# M8-SHT30.net
KiCad netlist of a schematic drawn in EAGLE
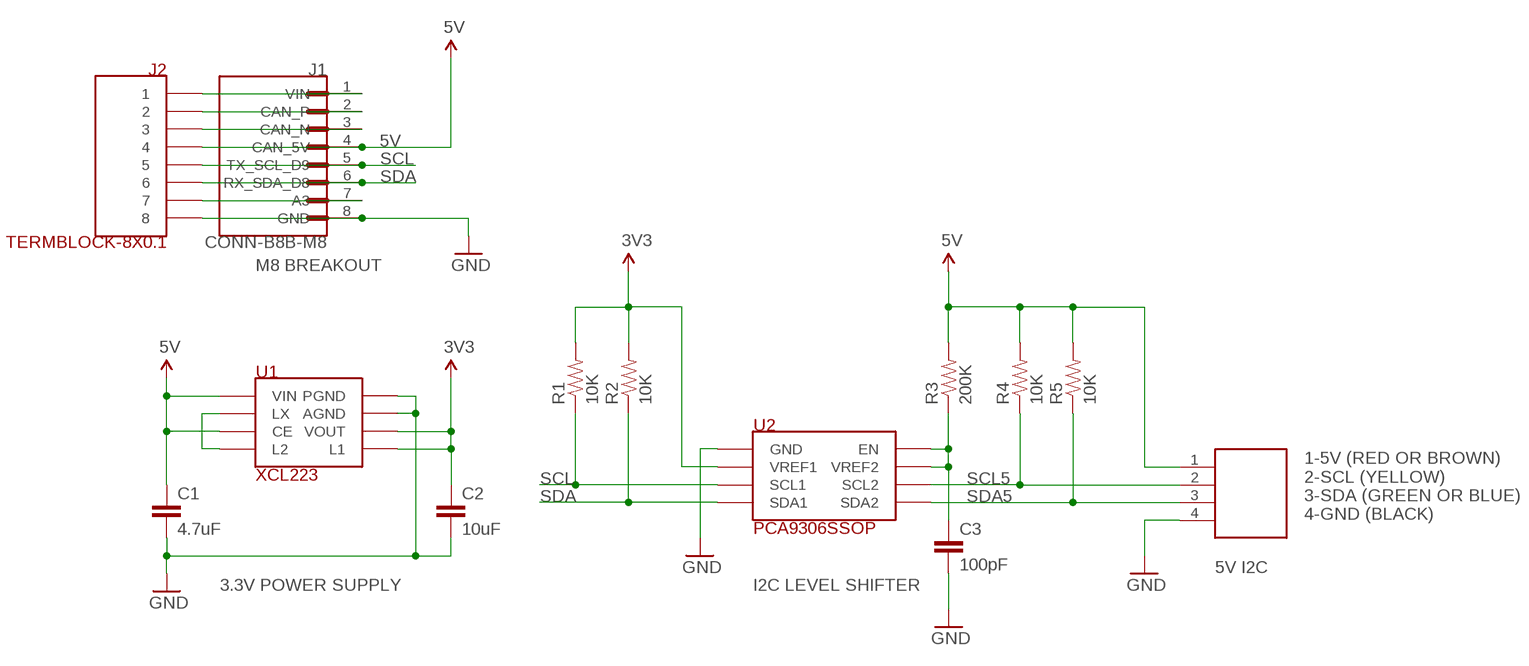
[diagram p0: schematic, sheet 1]

(export (version "E")
  (design (tool "Eeschema 10.0.6"))
  (components
    (comp (ref "C1")
      (value "4.7uF")
      (footprint "eagle-import:0603-CAP")
      (libsource (lib "eagle-import") (part "CAP-4.7UF-0603"))
    )
    (comp (ref "C2")
      (value "10uF")
      (footprint "eagle-import:0603-CAP")
      (libsource (lib "eagle-import") (part "CAP-10UF-0603"))
    )
    (comp (ref "C3")
      (value "100pF")
      (footprint "eagle-import:0603-CAP")
      (libsource (lib "eagle-import") (part "CAP-100PF-0603"))
    )
    (comp (ref "J1")
      (value "CONN-B8B-M8")
      (footprint "eagle-import:JST_B8B-PH-SM4-TB(LF)(SN)")
      (libsource (lib "eagle-import") (part "CONN-B8B-M8"))
    )
    (comp (ref "J2")
      (value "TERMBLOCK-8X0.1")
      (footprint "eagle-import:TERMBLOCK-8X0.1")
      (libsource (lib "eagle-import") (part "TERMBLOCK-8X0.1"))
    )
    (comp (ref "R1")
      (value "10K")
      (footprint "eagle-import:0603-RES")
      (libsource (lib "eagle-import") (part "RES-10K-06030603"))
    )
    (comp (ref "R2")
      (value "10K")
      (footprint "eagle-import:0603-RES")
      (libsource (lib "eagle-import") (part "RES-10K-06030603"))
    )
    (comp (ref "R3")
      (value "200K")
      (footprint "eagle-import:0603-RES")
      (libsource (lib "eagle-import") (part "RES-200K-0603"))
    )
    (comp (ref "R4")
      (value "10K")
      (footprint "eagle-import:0603-RES")
      (libsource (lib "eagle-import") (part "RES-10K-06030603"))
    )
    (comp (ref "R5")
      (value "10K")
      (footprint "eagle-import:0603-RES")
      (libsource (lib "eagle-import") (part "RES-10K-06030603"))
    )
    (comp (ref "U$1")
      (value "TERMBLOCK-4X0.15")
      (footprint "eagle-import:TERMBLOCK-4X0.15")
      (libsource (lib "eagle-import") (part "TERMBLOCK-4X0.15"))
    )
    (comp (ref "U1")
      (value "XCL223")
      (footprint "eagle-import:REG-XCL223-LESS-CREAM")
      (libsource (lib "eagle-import") (part "REG-XCL223"))
    )
    (comp (ref "U2")
      (value "PCA9306SSOP")
      (footprint "eagle-import:8-SSOP-TI")
      (libsource (lib "eagle-import") (part "PCA9306SSOP"))
    )
  )
  (nets
    (net (code "1") (name "/SCL") (class "Default")
      (node (ref "J1") (pin "5") (pinfunction "TX_SCL_D9_5") (pintype "passive"))
      (node (ref "J2") (pin "P$5") (pinfunction "5_P$5") (pintype "passive"))
      (node (ref "R1") (pin "1") (pinfunction "1_1") (pintype "passive"))
      (node (ref "U2") (pin "3") (pinfunction "SCL1_3") (pintype "bidirectional"))
    )
    (net (code "2") (name "/SCL5") (class "Default")
      (node (ref "R4") (pin "1") (pinfunction "1_1") (pintype "passive"))
      (node (ref "U$1") (pin "2") (pinfunction "2_2") (pintype "passive"))
      (node (ref "U2") (pin "6") (pinfunction "SCL2_6") (pintype "bidirectional"))
    )
    (net (code "3") (name "/SDA") (class "Default")
      (node (ref "J1") (pin "6") (pinfunction "RX_SDA_D8_6") (pintype "passive"))
      (node (ref "J2") (pin "P$6") (pinfunction "6_P$6") (pintype "passive"))
      (node (ref "R2") (pin "1") (pinfunction "1_1") (pintype "passive"))
      (node (ref "U2") (pin "4") (pinfunction "SDA1_4") (pintype "bidirectional"))
    )
    (net (code "4") (name "/SDA5") (class "Default")
      (node (ref "R5") (pin "1") (pinfunction "1_1") (pintype "passive"))
      (node (ref "U$1") (pin "3") (pinfunction "3_3") (pintype "passive"))
      (node (ref "U2") (pin "5") (pinfunction "SDA2_5") (pintype "bidirectional"))
    )
    (net (code "5") (name "3V3") (class "Default")
      (node (ref "C2") (pin "1") (pinfunction "1_1") (pintype "passive"))
      (node (ref "R1") (pin "2") (pinfunction "2_2") (pintype "passive"))
      (node (ref "R2") (pin "2") (pinfunction "2_2") (pintype "passive"))
      (node (ref "U1") (pin "3") (pinfunction "VOUT_3") (pintype "passive"))
      (node (ref "U1") (pin "7") (pinfunction "L1_7") (pintype "passive"))
      (node (ref "U2") (pin "2") (pinfunction "VREF1_2") (pintype "power_in"))
    )
    (net (code "6") (name "5V") (class "Default")
      (node (ref "C1") (pin "1") (pinfunction "1_1") (pintype "passive"))
      (node (ref "J1") (pin "4") (pinfunction "CAN_5V_4") (pintype "passive"))
      (node (ref "J2") (pin "P$4") (pinfunction "4_P$4") (pintype "passive"))
      (node (ref "R3") (pin "2") (pinfunction "2_2") (pintype "passive"))
      (node (ref "R4") (pin "2") (pinfunction "2_2") (pintype "passive"))
      (node (ref "R5") (pin "2") (pinfunction "2_2") (pintype "passive"))
      (node (ref "U$1") (pin "1") (pinfunction "1_1") (pintype "passive"))
      (node (ref "U1") (pin "4") (pinfunction "CE_4") (pintype "input"))
      (node (ref "U1") (pin "6") (pinfunction "VIN_6") (pintype "power_in"))
    )
    (net (code "7") (name "GND") (class "Default")
      (node (ref "C1") (pin "2") (pinfunction "2_2") (pintype "passive"))
      (node (ref "C2") (pin "2") (pinfunction "2_2") (pintype "passive"))
      (node (ref "C3") (pin "2") (pinfunction "2_2") (pintype "passive"))
      (node (ref "J1") (pin "8") (pinfunction "GND_8") (pintype "passive"))
      (node (ref "J2") (pin "P$8") (pinfunction "8_P$8") (pintype "passive"))
      (node (ref "U$1") (pin "4") (pinfunction "4_4") (pintype "passive"))
      (node (ref "U1") (pin "1") (pinfunction "PGND_1") (pintype "passive"))
      (node (ref "U1") (pin "2") (pinfunction "AGND_2") (pintype "passive"))
      (node (ref "U2") (pin "1") (pinfunction "GND_1") (pintype "passive"))
    )
    (net (code "8") (name "Net-(J1-A3)") (class "Default")
      (node (ref "J1") (pin "7") (pinfunction "A3_7") (pintype "passive"))
      (node (ref "J2") (pin "P$7") (pinfunction "7_P$7") (pintype "passive"))
    )
    (net (code "9") (name "Net-(J1-CAN_N)") (class "Default")
      (node (ref "J1") (pin "3") (pinfunction "CAN_N_3") (pintype "passive"))
      (node (ref "J2") (pin "P$3") (pinfunction "3_P$3") (pintype "passive"))
    )
    (net (code "10") (name "Net-(J1-CAN_P)") (class "Default")
      (node (ref "J1") (pin "2") (pinfunction "CAN_P_2") (pintype "passive"))
      (node (ref "J2") (pin "P$2") (pinfunction "2_P$2") (pintype "passive"))
    )
    (net (code "11") (name "Net-(J1-VIN)") (class "Default")
      (node (ref "J1") (pin "1") (pinfunction "VIN_1") (pintype "passive"))
      (node (ref "J2") (pin "P$1") (pinfunction "1_P$1") (pintype "passive"))
    )
    (net (code "12") (name "Net-(U1-L2)") (class "Default")
      (node (ref "U1") (pin "5") (pinfunction "LX_5") (pintype "passive"))
      (node (ref "U1") (pin "8") (pinfunction "L2_8") (pintype "passive"))
    )
    (net (code "13") (name "Net-(U2-EN)") (class "Default")
      (node (ref "C3") (pin "1") (pinfunction "1_1") (pintype "passive"))
      (node (ref "R3") (pin "1") (pinfunction "1_1") (pintype "passive"))
      (node (ref "U2") (pin "7") (pinfunction "VREF2_7") (pintype "input"))
      (node (ref "U2") (pin "8") (pinfunction "EN_8") (pintype "input"))
    )
  )
)
